# blds.net
KiCad netlist of a schematic drawn in Altium Designer
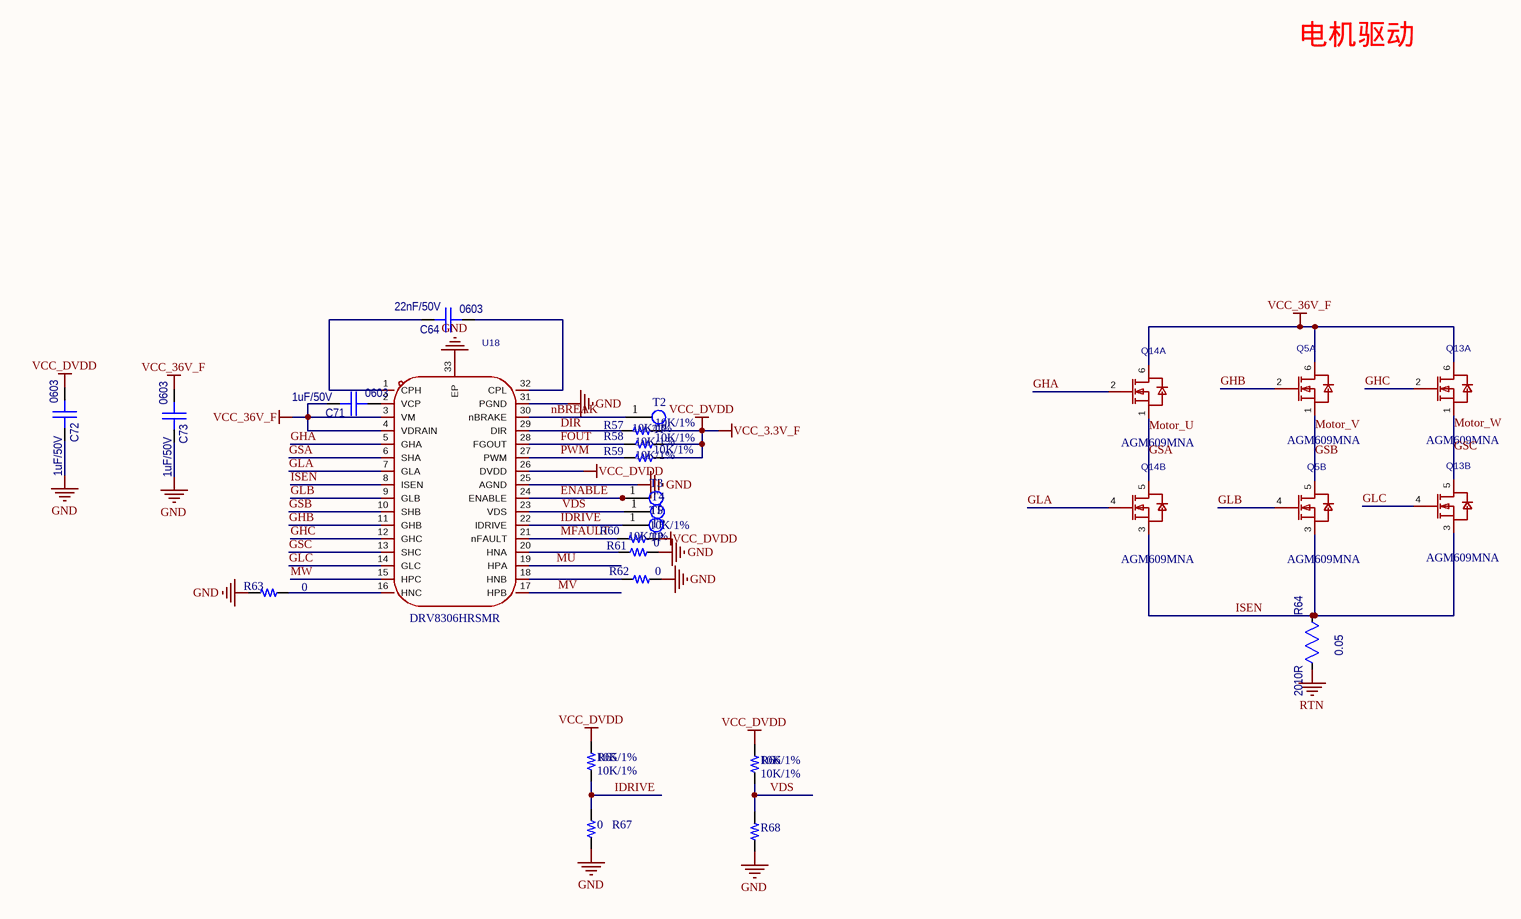
[diagram p0: blds.SchDoc]

(export (version "E")
  (design (tool "Eeschema 10.0.6"))
  (components
    (comp (ref "C64")
      (value "22nF/50V")
      (footprint "0603c")
      (description "Capacitor, MLCC")
      (fields (field (name "PACKAGE") "0603"))
      (libsource (lib "Karl") (part "Capacitor_0603"))
    )
    (comp (ref "C71")
      (value "1uF/50V")
      (footprint "0603C")
      (description "Capacitor, MLCC")
      (fields (field (name "PACKAGE") "0603"))
      (libsource (lib "Karl") (part "Capacitor_0603"))
    )
    (comp (ref "C72")
      (value "1uF/50V")
      (footprint "0603C")
      (description "Capacitor, MLCC")
      (fields (field (name "PACKAGE") "0603"))
      (libsource (lib "Karl") (part "Capacitor_0603"))
    )
    (comp (ref "C73")
      (value "1uF/50V")
      (footprint "0603C")
      (description "Capacitor, MLCC")
      (fields (field (name "PACKAGE") "0603"))
      (libsource (lib "Karl") (part "Capacitor_0603"))
    )
    (comp (ref "Q5")
      (value "AGM609MNA")
      (footprint "DFN-8_L5.5-W5.2-P1.27-LS6.0-BL-EP2")
      (libsource (lib "altium-import") (part "root_0_AGM609MNA_"))
    )
    (comp (ref "Q13")
      (value "AGM609MNA")
      (footprint "DFN-8_L5.5-W5.2-P1.27-LS6.0-BL-EP2")
      (libsource (lib "altium-import") (part "root_0_AGM609MNA_"))
    )
    (comp (ref "Q14")
      (value "AGM609MNA")
      (footprint "DFN-8_L5.5-W5.2-P1.27-LS6.0-BL-EP2")
      (libsource (lib "altium-import") (part "root_0_AGM609MNA_"))
    )
    (comp (ref "R57")
      (value "10K/1%")
      (footprint "0603R")
      (fields (field (name "ALTIUM_VALUE") "10K/1%"))
      (libsource (lib "JRJ_1") (part "R"))
    )
    (comp (ref "R58")
      (value "10K/1%")
      (footprint "0603R")
      (fields (field (name "ALTIUM_VALUE") "10K/1%"))
      (libsource (lib "JRJ_1") (part "R"))
    )
    (comp (ref "R59")
      (value "10K/1%")
      (footprint "0603R")
      (fields (field (name "ALTIUM_VALUE") "10K/1%"))
      (libsource (lib "JRJ_1") (part "R"))
    )
    (comp (ref "R60")
      (value "10K/1%")
      (footprint "0603R")
      (fields (field (name "ALTIUM_VALUE") "10K/1%"))
      (libsource (lib "JRJ_1") (part "R"))
    )
    (comp (ref "R61") (value "0") (footprint "0603R") (libsource (lib "JRJ_1") (part "R")))
    (comp (ref "R62") (value "0") (footprint "0603R") (libsource (lib "JRJ_1") (part "R")))
    (comp (ref "R63") (value "0") (footprint "0603R") (libsource (lib "JRJ_1") (part "R")))
    (comp (ref "R64")
      (value "0.05")
      (footprint "2010R")
      (description "Resistor, Standard")
      (fields (field (name "PACKAGE") "2010R"))
      (libsource (lib "Karl") (part "Resistor_0603"))
    )
    (comp (ref "R65")
      (value "10K/1%")
      (footprint "0603R")
      (fields (field (name "ALTIUM_VALUE") "10K/1%"))
      (libsource (lib "JRJ_1") (part "R"))
    )
    (comp (ref "R66")
      (value "10K/1%")
      (footprint "0603R")
      (fields (field (name "ALTIUM_VALUE") "10K/1%"))
      (libsource (lib "JRJ_1") (part "R"))
    )
    (comp (ref "R67") (value "0") (footprint "0603R") (libsource (lib "JRJ_1") (part "R")))
    (comp (ref "R68") (value "0") (footprint "0603R") (libsource (lib "JRJ_1") (part "R")))
    (comp (ref "T2") (value "TP") (footprint "TPd") (libsource (lib "Schlib_20110825") (part "TP")))
    (comp (ref "T3") (value "TP") (footprint "TPd") (libsource (lib "Schlib_20110825") (part "TP")))
    (comp (ref "T4") (value "TP") (footprint "TPd") (libsource (lib "Schlib_20110825") (part "TP")))
    (comp (ref "T5") (value "TP") (footprint "TPd") (libsource (lib "Schlib_20110825") (part "TP")))
    (comp (ref "U18")
      (value "DRV8306HRSMR")
      (footprint "VQFN-32_L4.0-W4.0-P0.40-BL-EP")
      (libsource (lib "altium-import") (part "root_0_DRV8306HRSMR_"))
    )
  )
  (nets
    (net (code "1") (name "/DIR") (class "Default")
      (node (ref "R57") (pin "1") (pintype "passive"))
      (node (ref "U18") (pin "29") (pinfunction "DIR_29") (pintype "passive"))
    )
    (net (code "2") (name "/ENABLE") (class "Default")
      (node (ref "T3") (pin "1") (pintype "passive"))
      (node (ref "U18") (pin "24") (pinfunction "ENABLE_24") (pintype "passive"))
    )
    (net (code "3") (name "/FOUT") (class "Default")
      (node (ref "R58") (pin "1") (pintype "passive"))
      (node (ref "U18") (pin "28") (pinfunction "FGOUT_28") (pintype "passive"))
    )
    (net (code "4") (name "/GHA") (class "Default")
      (node (ref "Q14") (pin "2") (pinfunction "G1_2") (pintype "passive"))
      (node (ref "U18") (pin "5") (pinfunction "GHA_5") (pintype "passive"))
    )
    (net (code "5") (name "/GHB") (class "Default")
      (node (ref "Q5") (pin "2") (pinfunction "G1_2") (pintype "passive"))
      (node (ref "U18") (pin "11") (pinfunction "GHB_11") (pintype "passive"))
    )
    (net (code "6") (name "/GHC") (class "Default")
      (node (ref "Q13") (pin "2") (pinfunction "G1_2") (pintype "passive"))
      (node (ref "U18") (pin "12") (pinfunction "GHC_12") (pintype "passive"))
    )
    (net (code "7") (name "/GLA") (class "Default")
      (node (ref "Q14") (pin "4") (pinfunction "G2_4") (pintype "passive"))
      (node (ref "U18") (pin "7") (pinfunction "GLA_7") (pintype "passive"))
    )
    (net (code "8") (name "/GLB") (class "Default")
      (node (ref "Q5") (pin "4") (pinfunction "G2_4") (pintype "passive"))
      (node (ref "U18") (pin "9") (pinfunction "GLB_9") (pintype "passive"))
    )
    (net (code "9") (name "/GLC") (class "Default")
      (node (ref "Q13") (pin "4") (pinfunction "G2_4") (pintype "passive"))
      (node (ref "U18") (pin "14") (pinfunction "GLC_14") (pintype "passive"))
    )
    (net (code "10") (name "/GSA") (class "Default")
      (node (ref "Q14") (pin "1") (pinfunction "S1_1") (pintype "passive"))
      (node (ref "Q14") (pin "5") (pinfunction "D2_5") (pintype "passive"))
      (node (ref "U18") (pin "6") (pinfunction "SHA_6") (pintype "passive"))
    )
    (net (code "11") (name "/GSB") (class "Default")
      (node (ref "Q5") (pin "1") (pinfunction "S1_1") (pintype "passive"))
      (node (ref "Q5") (pin "5") (pinfunction "D2_5") (pintype "passive"))
      (node (ref "U18") (pin "10") (pinfunction "SHB_10") (pintype "passive"))
    )
    (net (code "12") (name "/GSC") (class "Default")
      (node (ref "Q13") (pin "1") (pinfunction "S1_1") (pintype "passive"))
      (node (ref "Q13") (pin "5") (pinfunction "D2_5") (pintype "passive"))
      (node (ref "U18") (pin "13") (pinfunction "SHC_13") (pintype "passive"))
    )
    (net (code "13") (name "/IDRIVE") (class "Default")
      (node (ref "R65") (pin "2") (pintype "passive"))
      (node (ref "R67") (pin "1") (pintype "passive"))
      (node (ref "T5") (pin "1") (pintype "passive"))
      (node (ref "U18") (pin "22") (pinfunction "IDRIVE_22") (pintype "passive"))
    )
    (net (code "14") (name "/ISEN") (class "Default")
      (node (ref "Q13") (pin "3") (pinfunction "S2_3") (pintype "passive"))
      (node (ref "Q14") (pin "3") (pinfunction "S2_3") (pintype "passive"))
      (node (ref "Q5") (pin "3") (pinfunction "S2_3") (pintype "passive"))
      (node (ref "R64") (pin "2") (pinfunction "2_2") (pintype "passive"))
      (node (ref "U18") (pin "8") (pinfunction "ISEN_8") (pintype "passive"))
    )
    (net (code "15") (name "/MFAULT") (class "Default")
      (node (ref "R60") (pin "1") (pintype "passive"))
      (node (ref "U18") (pin "21") (pinfunction "nFAULT_21") (pintype "passive"))
    )
    (net (code "16") (name "/MU") (class "Default")
      (node (ref "U18") (pin "19") (pinfunction "HPA_19") (pintype "passive"))
    )
    (net (code "17") (name "/MV") (class "Default")
      (node (ref "U18") (pin "17") (pinfunction "HPB_17") (pintype "passive"))
    )
    (net (code "18") (name "/MW") (class "Default")
      (node (ref "U18") (pin "15") (pinfunction "HPC_15") (pintype "passive"))
    )
    (net (code "19") (name "/PWM") (class "Default")
      (node (ref "R59") (pin "1") (pintype "passive"))
      (node (ref "U18") (pin "27") (pinfunction "PWM_27") (pintype "passive"))
    )
    (net (code "20") (name "/VDS") (class "Default")
      (node (ref "R66") (pin "2") (pintype "passive"))
      (node (ref "R68") (pin "1") (pintype "passive"))
      (node (ref "T4") (pin "1") (pintype "passive"))
      (node (ref "U18") (pin "23") (pinfunction "VDS_23") (pintype "passive"))
    )
    (net (code "21") (name "/nBREAK") (class "Default")
      (node (ref "T2") (pin "1") (pintype "passive"))
      (node (ref "U18") (pin "30") (pinfunction "nBRAKE_30") (pintype "passive"))
    )
    (net (code "22") (name "GND") (class "Default")
      (node (ref "C72") (pin "2") (pinfunction "2_2") (pintype "passive"))
      (node (ref "C73") (pin "2") (pinfunction "2_2") (pintype "passive"))
      (node (ref "R61") (pin "2") (pintype "passive"))
      (node (ref "R62") (pin "2") (pintype "passive"))
      (node (ref "R63") (pin "2") (pintype "passive"))
      (node (ref "R67") (pin "2") (pintype "passive"))
      (node (ref "R68") (pin "2") (pintype "passive"))
      (node (ref "U18") (pin "25") (pinfunction "AGND_25") (pintype "passive"))
      (node (ref "U18") (pin "31") (pinfunction "PGND_31") (pintype "passive"))
      (node (ref "U18") (pin "33") (pinfunction "EP_33") (pintype "passive"))
    )
    (net (code "23") (name "Net-(U18-CPH)") (class "Default")
      (node (ref "C64") (pin "2") (pinfunction "2_2") (pintype "passive"))
      (node (ref "U18") (pin "1") (pinfunction "CPH_1") (pintype "passive"))
    )
    (net (code "24") (name "Net-(U18-CPL)") (class "Default")
      (node (ref "C64") (pin "1") (pinfunction "1_1") (pintype "passive"))
      (node (ref "U18") (pin "32") (pinfunction "CPL_32") (pintype "passive"))
    )
    (net (code "25") (name "Net-(U18-HNA)") (class "Default")
      (node (ref "R61") (pin "1") (pintype "passive"))
      (node (ref "U18") (pin "20") (pinfunction "HNA_20") (pintype "passive"))
    )
    (net (code "26") (name "Net-(U18-HNB)") (class "Default")
      (node (ref "R62") (pin "1") (pintype "passive"))
      (node (ref "U18") (pin "18") (pinfunction "HNB_18") (pintype "passive"))
    )
    (net (code "27") (name "Net-(U18-HNC)") (class "Default")
      (node (ref "R63") (pin "1") (pintype "passive"))
      (node (ref "U18") (pin "16") (pinfunction "HNC_16") (pintype "passive"))
    )
    (net (code "28") (name "Net-(U18-VCP)") (class "Default")
      (node (ref "C71") (pin "1") (pinfunction "1_1") (pintype "passive"))
      (node (ref "U18") (pin "2") (pinfunction "VCP_2") (pintype "passive"))
    )
    (net (code "29") (name "RTN") (class "Default")
      (node (ref "R64") (pin "1") (pinfunction "1_1") (pintype "passive"))
    )
    (net (code "30") (name "VCC_3.3V_F") (class "Default")
      (node (ref "C72") (pin "1") (pinfunction "1_1") (pintype "passive"))
      (node (ref "R57") (pin "2") (pintype "passive"))
      (node (ref "R58") (pin "2") (pintype "passive"))
      (node (ref "R59") (pin "2") (pintype "passive"))
      (node (ref "R60") (pin "2") (pintype "passive"))
      (node (ref "R65") (pin "1") (pintype "passive"))
      (node (ref "R66") (pin "1") (pintype "passive"))
      (node (ref "U18") (pin "26") (pinfunction "DVDD_26") (pintype "passive"))
    )
    (net (code "31") (name "VCC_36V_F") (class "Default")
      (node (ref "C71") (pin "2") (pinfunction "2_2") (pintype "passive"))
      (node (ref "C73") (pin "1") (pinfunction "1_1") (pintype "passive"))
      (node (ref "Q13") (pin "6") (pinfunction "D1_6") (pintype "passive"))
      (node (ref "Q14") (pin "6") (pinfunction "D1_6") (pintype "passive"))
      (node (ref "Q5") (pin "6") (pinfunction "D1_6") (pintype "passive"))
      (node (ref "U18") (pin "3") (pinfunction "VM_3") (pintype "passive"))
      (node (ref "U18") (pin "4") (pinfunction "VDRAIN_4") (pintype "passive"))
    )
  )
)
